# 1_ADSTM32-Power.net
KiCad netlist of a schematic drawn in Altium Designer
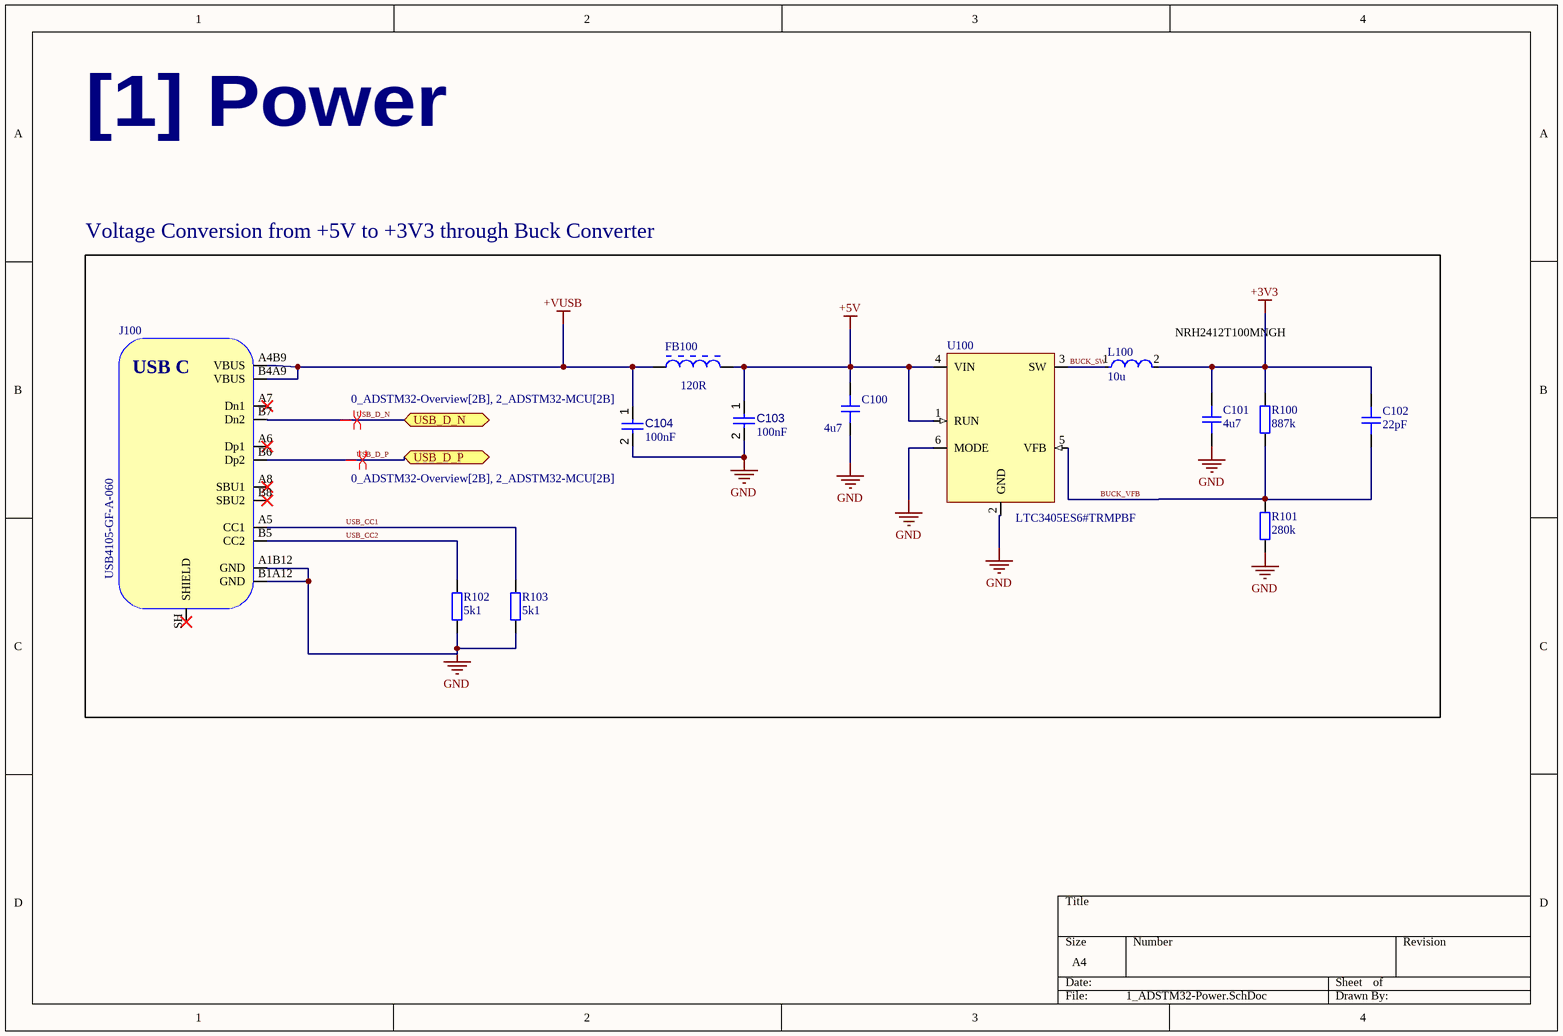
[diagram p0: 1_ADSTM32-Power.SchDoc]

(export (version "E")
  (design (tool "Eeschema 10.0.6"))
  (components
    (comp (ref "C100")
      (value "4u7")
      (footprint "CAP_0805")
      (description "Capacitor SMD 0805")
      (libsource (lib "Schematic-Lib-PhilsLab") (part "CAP_0805"))
    )
    (comp (ref "C101")
      (value "4u7")
      (footprint "CAP_0805")
      (description "Capacitor SMD 0805")
      (libsource (lib "Schematic-Lib-PhilsLab") (part "CAP_0805"))
    )
    (comp (ref "C102")
      (value "22pF")
      (footprint "CAP_0603")
      (description "Capacitor SMD 0603")
      (libsource (lib "Schematic-Lib-PhilsLab") (part "CAP_0603"))
    )
    (comp (ref "C103")
      (value "100nF")
      (footprint "CAPC1608X90X40NL10T20")
      (description "Chip Capacitor, 100 nF, +/- 10%, 50 V, 0603 (1608 Metric)")
      (fields (field (name "TOLERANCE") "10%") (field (name "Comment") "Capacitor 100 nF +/-10% 50 V 0603"))
      (libsource (lib "Technische Universität Darmstadt -  Institut für Stromrichtertechnik und Antriebsregelung") (part "CAP-NP-2"))
    )
    (comp (ref "C104")
      (value "100nF")
      (footprint "CAPC1608X90X40NL10T20")
      (description "Chip Capacitor, 100 nF, +/- 10%, 50 V, 0603 (1608 Metric)")
      (fields (field (name "TOLERANCE") "10%") (field (name "Comment") "Capacitor 100 nF +/-10% 50 V 0603"))
      (libsource (lib "Technische Universität Darmstadt -  Institut für Stromrichtertechnik und Antriebsregelung") (part "CAP-NP-2"))
    )
    (comp (ref "FB100")
      (value "120R")
      (footprint "INDC2013X105X50ML20T20")
      (description "Chip Ferrite Bead, 120 Ohm,")
      (fields (field (name "TOLERANCE") "25%") (field (name "MANUFACTURER") "Murata"))
      (libsource (lib "Technische Universität Darmstadt -  Institut für Stromrichtertechnik und Antriebsregelung") (part "IND-FB-2"))
    )
    (comp (ref "J100")
      (value "USB4105-GF-A-060")
      (footprint "USB4105-GF-A-060")
      (description "USB Connector Type C SMT 12 Pin")
      (fields (field (name "MANUFACTURER") "GCT"))
      (libsource (lib "Schematic-Lib-PhilsLab") (part "USB4105-GF-A-060"))
    )
    (comp (ref "L100")
      (value "10u")
      (footprint "FP-NRH2412-MFG")
      (description "Shielded Wirewound Inductor 10uH 20% 0.51A 0.72Ω SMD")
      (fields (field (name "TOLERANCE") "20%"))
      (libsource (lib "Altium Content Vault") (part "725321dda6339637d4d059423bc1c3c"))
    )
    (comp (ref "R100")
      (value "887k")
      (footprint "RES_0603")
      (description "Resistor SMD 0603")
      (libsource (lib "Schematic-Lib-PhilsLab") (part "RES_0603"))
    )
    (comp (ref "R101")
      (value "280k")
      (footprint "RES_0603")
      (description "Resistor SMD 0603")
      (libsource (lib "Schematic-Lib-PhilsLab") (part "RES_0603"))
    )
    (comp (ref "R102")
      (value "5k1")
      (footprint "RES_0603")
      (description "Resistor SMD 0603")
      (libsource (lib "Schematic-Lib-PhilsLab") (part "RES_0603"))
    )
    (comp (ref "R103")
      (value "5k1")
      (footprint "RES_0603")
      (description "Resistor SMD 0603")
      (libsource (lib "Schematic-Lib-PhilsLab") (part "RES_0603"))
    )
    (comp (ref "U100")
      (value "LTC3405ES6#TRMPBF")
      (footprint "SOT-23-6")
      (description "1.5MHz, 300mA\r\nSynchronous Step-Down\r\nRegulator in ThinSOT")
      (fields (field (name "MANUFACTURER") "Analog Devices"))
      (libsource (lib "Schematic-Lib-PhilsLab") (part "LTC3405ES6#TRMPBF"))
    )
  )
  (nets
    (net (code "1") (name "+3V3") (class "Default")
      (node (ref "C101") (pin "2") (pinfunction "2_2") (pintype "passive"))
      (node (ref "C102") (pin "2") (pinfunction "2_2") (pintype "passive"))
      (node (ref "L100") (pin "2") (pinfunction "2_2") (pintype "passive"))
      (node (ref "R100") (pin "2") (pinfunction "2_2") (pintype "passive"))
    )
    (net (code "2") (name "+5V") (class "Default")
      (node (ref "C100") (pin "2") (pinfunction "2_2") (pintype "passive"))
      (node (ref "C103") (pin "1") (pinfunction "1_1") (pintype "passive"))
      (node (ref "FB100") (pin "2") (pinfunction "2_2") (pintype "passive"))
      (node (ref "U100") (pin "1") (pinfunction "RUN_1") (pintype "input"))
      (node (ref "U100") (pin "4") (pinfunction "VIN_4") (pintype "power_in"))
    )
    (net (code "3") (name "+VUSB") (class "Default")
      (node (ref "C104") (pin "1") (pinfunction "1_1") (pintype "passive"))
      (node (ref "FB100") (pin "1") (pinfunction "1_1") (pintype "passive"))
      (node (ref "J100") (pin "A4B9") (pinfunction "VBUS_A4B9") (pintype "passive"))
      (node (ref "J100") (pin "B4A9") (pinfunction "VBUS_B4A9") (pintype "passive"))
    )
    (net (code "4") (name "/BUCK_SW") (class "Default")
      (node (ref "L100") (pin "1") (pinfunction "1_1") (pintype "passive"))
      (node (ref "U100") (pin "3") (pinfunction "SW_3") (pintype "power_in"))
    )
    (net (code "5") (name "/BUCK_VFB") (class "Default")
      (node (ref "C102") (pin "1") (pinfunction "1_1") (pintype "passive"))
      (node (ref "R100") (pin "1") (pinfunction "1_1") (pintype "passive"))
      (node (ref "R101") (pin "2") (pinfunction "2_2") (pintype "passive"))
      (node (ref "U100") (pin "5") (pinfunction "VFB_5") (pintype "input"))
    )
    (net (code "6") (name "/USB_CC1") (class "Default")
      (node (ref "J100") (pin "A5") (pinfunction "CC1_A5") (pintype "passive"))
      (node (ref "R103") (pin "2") (pinfunction "2_2") (pintype "passive"))
    )
    (net (code "7") (name "/USB_CC2") (class "Default")
      (node (ref "J100") (pin "B5") (pinfunction "CC2_B5") (pintype "passive"))
      (node (ref "R102") (pin "2") (pinfunction "2_2") (pintype "passive"))
    )
    (net (code "8") (name "/USB_D_N") (class "Default")
      (node (ref "J100") (pin "B7") (pinfunction "Dn2_B7") (pintype "passive"))
    )
    (net (code "9") (name "/USB_D_P") (class "Default")
      (node (ref "J100") (pin "B6") (pinfunction "Dp2_B6") (pintype "passive"))
    )
    (net (code "10") (name "GND") (class "Default")
      (node (ref "C100") (pin "1") (pinfunction "1_1") (pintype "passive"))
      (node (ref "C101") (pin "1") (pinfunction "1_1") (pintype "passive"))
      (node (ref "C103") (pin "2") (pinfunction "2_2") (pintype "passive"))
      (node (ref "C104") (pin "2") (pinfunction "2_2") (pintype "passive"))
      (node (ref "J100") (pin "A1B12") (pinfunction "GND_A1B12") (pintype "passive"))
      (node (ref "J100") (pin "B1A12") (pinfunction "GND_B1A12") (pintype "passive"))
      (node (ref "R101") (pin "1") (pinfunction "1_1") (pintype "passive"))
      (node (ref "R102") (pin "1") (pinfunction "1_1") (pintype "passive"))
      (node (ref "R103") (pin "1") (pinfunction "1_1") (pintype "passive"))
      (node (ref "U100") (pin "2") (pinfunction "GND_2") (pintype "power_in"))
      (node (ref "U100") (pin "6") (pinfunction "MODE_6") (pintype "passive"))
    )
    (net (code "11") (name "unconnected-(J100-Dn1-PadA7)") (class "Default")
      (node (ref "J100") (pin "A7") (pinfunction "Dn1_A7") (pintype "passive+no_connect"))
    )
    (net (code "12") (name "unconnected-(J100-Dp1-PadA6)") (class "Default")
      (node (ref "J100") (pin "A6") (pinfunction "Dp1_A6") (pintype "passive+no_connect"))
    )
    (net (code "13") (name "unconnected-(J100-SBU1-PadA8)") (class "Default")
      (node (ref "J100") (pin "A8") (pinfunction "SBU1_A8") (pintype "passive+no_connect"))
    )
    (net (code "14") (name "unconnected-(J100-SBU2-PadB8)") (class "Default")
      (node (ref "J100") (pin "B8") (pinfunction "SBU2_B8") (pintype "passive+no_connect"))
    )
    (net (code "15") (name "unconnected-(J100-SHIELD-PadSH)") (class "Default")
      (node (ref "J100") (pin "SH") (pinfunction "SHIELD_SH") (pintype "passive+no_connect"))
    )
  )
)
